# tetris.net
KiCad netlist of a schematic drawn in EAGLE
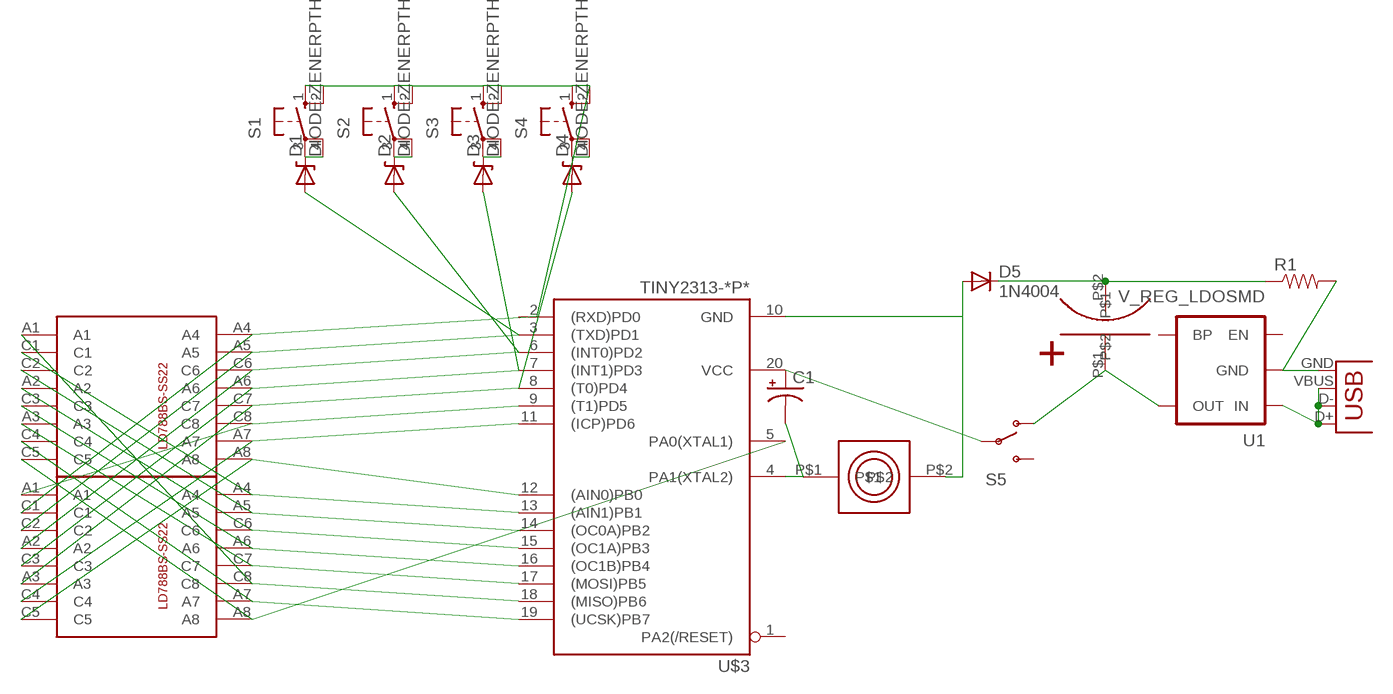
[diagram p0: schematic, sheet 1]

(export (version "E")
  (design (tool "Eeschema 10.0.6"))
  (components
    (comp (ref "C1")
      (value "CAP_POLPTH1")
      (footprint "eagle-import:CPOL-RADIAL-100UF-25V")
      (libsource (lib "eagle-import") (part "CAP_POLPTH1"))
    )
    (comp (ref "D1")
      (value "DIODE-ZENERPTH")
      (footprint "eagle-import:DIODE-ZENER")
      (libsource (lib "eagle-import") (part "DIODE-ZENERPTH"))
    )
    (comp (ref "D2")
      (value "DIODE-ZENERPTH")
      (footprint "eagle-import:DIODE-ZENER")
      (libsource (lib "eagle-import") (part "DIODE-ZENERPTH"))
    )
    (comp (ref "D3")
      (value "DIODE-ZENERPTH")
      (footprint "eagle-import:DIODE-ZENER")
      (libsource (lib "eagle-import") (part "DIODE-ZENERPTH"))
    )
    (comp (ref "D4")
      (value "DIODE-ZENERPTH")
      (footprint "eagle-import:DIODE-ZENER")
      (libsource (lib "eagle-import") (part "DIODE-ZENERPTH"))
    )
    (comp (ref "D5")
      (value "1N4004")
      (footprint "eagle-import:DO41-10")
      (libsource (lib "eagle-import") (part "1N4004"))
    )
    (comp (ref "R1")
      (value "RESISTORPTH1")
      (footprint "eagle-import:AXIAL-0.3")
      (libsource (lib "eagle-import") (part "RESISTORPTH1"))
    )
    (comp (ref "S1")
      (value "10-XX")
      (footprint "eagle-import:B3F-10XX")
      (fields (field (name "MPN") "B3F-1000"))
      (libsource (lib "eagle-import") (part "10-XX"))
    )
    (comp (ref "S2")
      (value "10-XX")
      (footprint "eagle-import:B3F-10XX")
      (fields (field (name "MPN") "B3F-1000"))
      (libsource (lib "eagle-import") (part "10-XX"))
    )
    (comp (ref "S3")
      (value "10-XX")
      (footprint "eagle-import:B3F-10XX")
      (fields (field (name "MPN") "B3F-1000"))
      (libsource (lib "eagle-import") (part "10-XX"))
    )
    (comp (ref "S4")
      (value "10-XX")
      (footprint "eagle-import:B3F-10XX")
      (fields (field (name "MPN") "B3F-1000"))
      (libsource (lib "eagle-import") (part "10-XX"))
    )
    (comp (ref "S5")
      (value "SWITCH-SPSTSMD2")
      (footprint "eagle-import:SWITCH-SPDT-SMD")
      (libsource (lib "eagle-import") (part "SWITCH-SPSTSMD2"))
    )
    (comp (ref "U$1")
      (value "LD788BS-SS22")
      (footprint "eagle-import:LD788BS-SS22")
      (libsource (lib "eagle-import") (part "LD788BS-SS22"))
    )
    (comp (ref "U$2")
      (value "LD788BS-SS22")
      (footprint "eagle-import:LD788BS-SS22")
      (libsource (lib "eagle-import") (part "LD788BS-SS22"))
    )
    (comp (ref "U$3")
      (value "TINY2313-*P*")
      (footprint "eagle-import:DIL20")
      (libsource (lib "eagle-import") (part "TINY2313-P"))
    )
    (comp (ref "U$4")
      (value "I-80450RF")
      (footprint "eagle-import:ISK4.1K_I-80450RF_I2G")
      (libsource (lib "eagle-import") (part "I-80450RF"))
    )
    (comp (ref "U$5")
      (value "NICHICON_12F")
      (footprint "eagle-import:NICHICON_10X30")
      (libsource (lib "eagle-import") (part "NICHICON_12F"))
    )
    (comp (ref "U1")
      (value "V_REG_LDOSMD")
      (footprint "eagle-import:SOT23-5")
      (libsource (lib "eagle-import") (part "V_REG_LDOSMD"))
    )
    (comp (ref "X1")
      (value "USB-MICROB")
      (footprint "eagle-import:USB-MICROB")
      (libsource (lib "eagle-import") (part "USB-MICROB"))
    )
  )
  (nets
    (net (code "1") (name "Net-(C1-+)") (class "Default")
      (node (ref "C1") (pin "1") (pinfunction "+_1") (pintype "passive"))
      (node (ref "S5") (pin "2") (pinfunction "P_2") (pintype "passive"))
      (node (ref "U$3") (pin "20") (pinfunction "VCC_20") (pintype "power_in"))
    )
    (net (code "2") (name "Net-(C1--)") (class "Default")
      (node (ref "C1") (pin "2") (pinfunction "-_2") (pintype "passive"))
      (node (ref "U$3") (pin "4") (pinfunction "PA1(XTAL2)_4") (pintype "bidirectional"))
      (node (ref "U$4") (pin "P$1") (pinfunction "P$1_P$1") (pintype "bidirectional"))
    )
    (net (code "3") (name "Net-(D1-A)") (class "Default")
      (node (ref "D1") (pin "P$2") (pinfunction "A_P$2") (pintype "passive"))
      (node (ref "U$1") (pin "C2") (pinfunction "C2_C2") (pintype "bidirectional"))
      (node (ref "U$2") (pin "A5") (pinfunction "A5_A5") (pintype "bidirectional"))
      (node (ref "U$3") (pin "3") (pinfunction "(TXD)PD1_3") (pintype "bidirectional"))
    )
    (net (code "4") (name "Net-(D1-C)") (class "Default")
      (node (ref "D1") (pin "P$1") (pinfunction "C_P$1") (pintype "passive"))
      (node (ref "S1") (pin "3") (pinfunction "P_3") (pintype "passive"))
      (node (ref "S1") (pin "4") (pinfunction "P1_4") (pintype "passive"))
    )
    (net (code "5") (name "Net-(D2-A)") (class "Default")
      (node (ref "D2") (pin "P$2") (pinfunction "A_P$2") (pintype "passive"))
      (node (ref "U$1") (pin "A2") (pinfunction "A2_A2") (pintype "bidirectional"))
      (node (ref "U$2") (pin "C6") (pinfunction "C6_C6") (pintype "bidirectional"))
      (node (ref "U$3") (pin "6") (pinfunction "(INT0)PD2_6") (pintype "bidirectional"))
    )
    (net (code "6") (name "Net-(D2-C)") (class "Default")
      (node (ref "D2") (pin "P$1") (pinfunction "C_P$1") (pintype "passive"))
      (node (ref "S2") (pin "3") (pinfunction "P_3") (pintype "passive"))
      (node (ref "S2") (pin "4") (pinfunction "P1_4") (pintype "passive"))
    )
    (net (code "7") (name "Net-(D3-A)") (class "Default")
      (node (ref "D3") (pin "P$2") (pinfunction "A_P$2") (pintype "passive"))
      (node (ref "U$1") (pin "C3") (pinfunction "C3_C3") (pintype "bidirectional"))
      (node (ref "U$2") (pin "A6") (pinfunction "A6_A6") (pintype "bidirectional"))
      (node (ref "U$3") (pin "7") (pinfunction "(INT1)PD3_7") (pintype "bidirectional"))
    )
    (net (code "8") (name "Net-(D3-C)") (class "Default")
      (node (ref "D3") (pin "P$1") (pinfunction "C_P$1") (pintype "passive"))
      (node (ref "S3") (pin "3") (pinfunction "P_3") (pintype "passive"))
      (node (ref "S3") (pin "4") (pinfunction "P1_4") (pintype "passive"))
    )
    (net (code "9") (name "Net-(D4-A)") (class "Default")
      (node (ref "D4") (pin "P$2") (pinfunction "A_P$2") (pintype "passive"))
      (node (ref "U$1") (pin "A3") (pinfunction "A3_A3") (pintype "bidirectional"))
      (node (ref "U$2") (pin "C7") (pinfunction "C7_C7") (pintype "bidirectional"))
      (node (ref "U$3") (pin "8") (pinfunction "(T0)PD4_8") (pintype "bidirectional"))
    )
    (net (code "10") (name "Net-(D4-C)") (class "Default")
      (node (ref "D4") (pin "P$1") (pinfunction "C_P$1") (pintype "passive"))
      (node (ref "S4") (pin "3") (pinfunction "P_3") (pintype "passive"))
      (node (ref "S4") (pin "4") (pinfunction "P1_4") (pintype "passive"))
    )
    (net (code "11") (name "Net-(R1-1)") (class "Default")
      (node (ref "D5") (pin "C") (pinfunction "C_C") (pintype "passive"))
      (node (ref "R1") (pin "P$1") (pinfunction "1_P$1") (pintype "passive"))
      (node (ref "U$5") (pin "P$2") (pinfunction "P$2_P$2") (pintype "bidirectional"))
    )
    (net (code "12") (name "Net-(R1-2)") (class "Default")
      (node (ref "R1") (pin "P$2") (pinfunction "2_P$2") (pintype "passive"))
      (node (ref "U1") (pin "2") (pinfunction "GND_2") (pintype "input"))
      (node (ref "X1") (pin "GND") (pinfunction "GND_GND") (pintype "bidirectional"))
    )
    (net (code "13") (name "Net-(S1-S)") (class "Default")
      (node (ref "S1") (pin "1") (pinfunction "S_1") (pintype "passive"))
      (node (ref "S1") (pin "2") (pinfunction "S1_2") (pintype "passive"))
      (node (ref "S2") (pin "1") (pinfunction "S_1") (pintype "passive"))
      (node (ref "S2") (pin "2") (pinfunction "S1_2") (pintype "passive"))
      (node (ref "S3") (pin "1") (pinfunction "S_1") (pintype "passive"))
      (node (ref "S3") (pin "2") (pinfunction "S1_2") (pintype "passive"))
      (node (ref "S4") (pin "1") (pinfunction "S_1") (pintype "passive"))
      (node (ref "S4") (pin "2") (pinfunction "S1_2") (pintype "passive"))
      (node (ref "U$1") (pin "C1") (pinfunction "C1_C1") (pintype "bidirectional"))
      (node (ref "U$2") (pin "A4") (pinfunction "A4_A4") (pintype "bidirectional"))
    )
    (net (code "14") (name "Net-(S5-O)") (class "Default")
      (node (ref "S5") (pin "1") (pinfunction "O_1") (pintype "passive"))
      (node (ref "U$5") (pin "P$1") (pinfunction "P$1_P$1") (pintype "bidirectional"))
      (node (ref "U1") (pin "5") (pinfunction "OUT_5") (pintype "passive"))
    )
    (net (code "15") (name "Net-(U$3-(AIN0)PB0)") (class "Default")
      (node (ref "U$1") (pin "C5") (pinfunction "C5_C5") (pintype "bidirectional"))
      (node (ref "U$2") (pin "A8") (pinfunction "A8_A8") (pintype "bidirectional"))
      (node (ref "U$3") (pin "12") (pinfunction "(AIN0)PB0_12") (pintype "bidirectional"))
    )
    (net (code "16") (name "Net-(U$3-(AIN1)PB1)") (class "Default")
      (node (ref "U$1") (pin "A4") (pinfunction "A4_A4") (pintype "bidirectional"))
      (node (ref "U$2") (pin "C1") (pinfunction "C1_C1") (pintype "bidirectional"))
      (node (ref "U$3") (pin "13") (pinfunction "(AIN1)PB1_13") (pintype "bidirectional"))
    )
    (net (code "17") (name "Net-(U$3-(ICP)PD6)") (class "Default")
      (node (ref "U$1") (pin "C4") (pinfunction "C4_C4") (pintype "bidirectional"))
      (node (ref "U$2") (pin "A7") (pinfunction "A7_A7") (pintype "bidirectional"))
      (node (ref "U$3") (pin "11") (pinfunction "(ICP)PD6_11") (pintype "bidirectional"))
    )
    (net (code "18") (name "Net-(U$3-(MISO)PB6)") (class "Default")
      (node (ref "U$1") (pin "C8") (pinfunction "C8_C8") (pintype "bidirectional"))
      (node (ref "U$2") (pin "A1") (pinfunction "A1_A1") (pintype "bidirectional"))
      (node (ref "U$3") (pin "18") (pinfunction "(MISO)PB6_18") (pintype "bidirectional"))
    )
    (net (code "19") (name "Net-(U$3-(MOSI)PB5)") (class "Default")
      (node (ref "U$1") (pin "C7") (pinfunction "C7_C7") (pintype "bidirectional"))
      (node (ref "U$2") (pin "A3") (pinfunction "A3_A3") (pintype "bidirectional"))
      (node (ref "U$3") (pin "17") (pinfunction "(MOSI)PB5_17") (pintype "bidirectional"))
    )
    (net (code "20") (name "Net-(U$3-(OC0A)PB2)") (class "Default")
      (node (ref "U$1") (pin "A5") (pinfunction "A5_A5") (pintype "bidirectional"))
      (node (ref "U$2") (pin "C2") (pinfunction "C2_C2") (pintype "bidirectional"))
      (node (ref "U$3") (pin "14") (pinfunction "(OC0A)PB2_14") (pintype "bidirectional"))
    )
    (net (code "21") (name "Net-(U$3-(OC1A)PB3)") (class "Default")
      (node (ref "U$1") (pin "C6") (pinfunction "C6_C6") (pintype "bidirectional"))
      (node (ref "U$2") (pin "A2") (pinfunction "A2_A2") (pintype "bidirectional"))
      (node (ref "U$3") (pin "15") (pinfunction "(OC1A)PB3_15") (pintype "bidirectional"))
    )
    (net (code "22") (name "Net-(U$3-(OC1B)PB4)") (class "Default")
      (node (ref "U$1") (pin "A6") (pinfunction "A6_A6") (pintype "bidirectional"))
      (node (ref "U$2") (pin "C3") (pinfunction "C3_C3") (pintype "bidirectional"))
      (node (ref "U$3") (pin "16") (pinfunction "(OC1B)PB4_16") (pintype "bidirectional"))
    )
    (net (code "23") (name "Net-(U$3-(T1)PD5)") (class "Default")
      (node (ref "U$1") (pin "A1") (pinfunction "A1_A1") (pintype "bidirectional"))
      (node (ref "U$2") (pin "C8") (pinfunction "C8_C8") (pintype "bidirectional"))
      (node (ref "U$3") (pin "9") (pinfunction "(T1)PD5_9") (pintype "bidirectional"))
    )
    (net (code "24") (name "Net-(U$3-(UCSK)PB7)") (class "Default")
      (node (ref "U$1") (pin "A7") (pinfunction "A7_A7") (pintype "bidirectional"))
      (node (ref "U$2") (pin "C4") (pinfunction "C4_C4") (pintype "bidirectional"))
      (node (ref "U$3") (pin "19") (pinfunction "(UCSK)PB7_19") (pintype "bidirectional"))
    )
    (net (code "25") (name "Net-(U$3-GND)") (class "Default")
      (node (ref "D5") (pin "A") (pinfunction "A_A") (pintype "passive"))
      (node (ref "U$3") (pin "10") (pinfunction "GND_10") (pintype "power_in"))
      (node (ref "U$4") (pin "P$2") (pinfunction "P$2_P$2") (pintype "bidirectional"))
    )
    (net (code "26") (name "Net-(U$3-PA0(XTAL1))") (class "Default")
      (node (ref "U$1") (pin "A8") (pinfunction "A8_A8") (pintype "bidirectional"))
      (node (ref "U$2") (pin "C5") (pinfunction "C5_C5") (pintype "bidirectional"))
      (node (ref "U$3") (pin "5") (pinfunction "PA0(XTAL1)_5") (pintype "bidirectional"))
    )
    (net (code "27") (name "Net-(U1-IN)") (class "Default")
      (node (ref "U1") (pin "1") (pinfunction "IN_1") (pintype "input"))
      (node (ref "X1") (pin "D+") (pinfunction "D+_D+") (pintype "bidirectional"))
      (node (ref "X1") (pin "D-") (pinfunction "D-_D-") (pintype "bidirectional"))
      (node (ref "X1") (pin "VBUS") (pinfunction "VBUS_VBUS") (pintype "bidirectional"))
    )
    (net (code "28") (name "unconnected-(S5-S-Pad3)") (class "Default")
      (node (ref "S5") (pin "3") (pinfunction "S_3") (pintype "passive"))
    )
    (net (code "29") (name "unconnected-(U$3-(RXD)PD0-Pad2)") (class "Default")
      (node (ref "U$3") (pin "2") (pinfunction "(RXD)PD0_2") (pintype "bidirectional"))
    )
    (net (code "30") (name "unconnected-(U$3-PA2({slash}RESET)-Pad1)") (class "Default")
      (node (ref "U$3") (pin "1") (pinfunction "PA2(/RESET)_1") (pintype "input"))
    )
    (net (code "31") (name "unconnected-(U1-BP-Pad4)") (class "Default")
      (node (ref "U1") (pin "4") (pinfunction "BP_4") (pintype "input"))
    )
    (net (code "32") (name "unconnected-(U1-EN-Pad3)") (class "Default")
      (node (ref "U1") (pin "3") (pinfunction "EN_3") (pintype "input"))
    )
  )
)
